# V4.net
KiCad netlist of a schematic drawn in Altium Designer
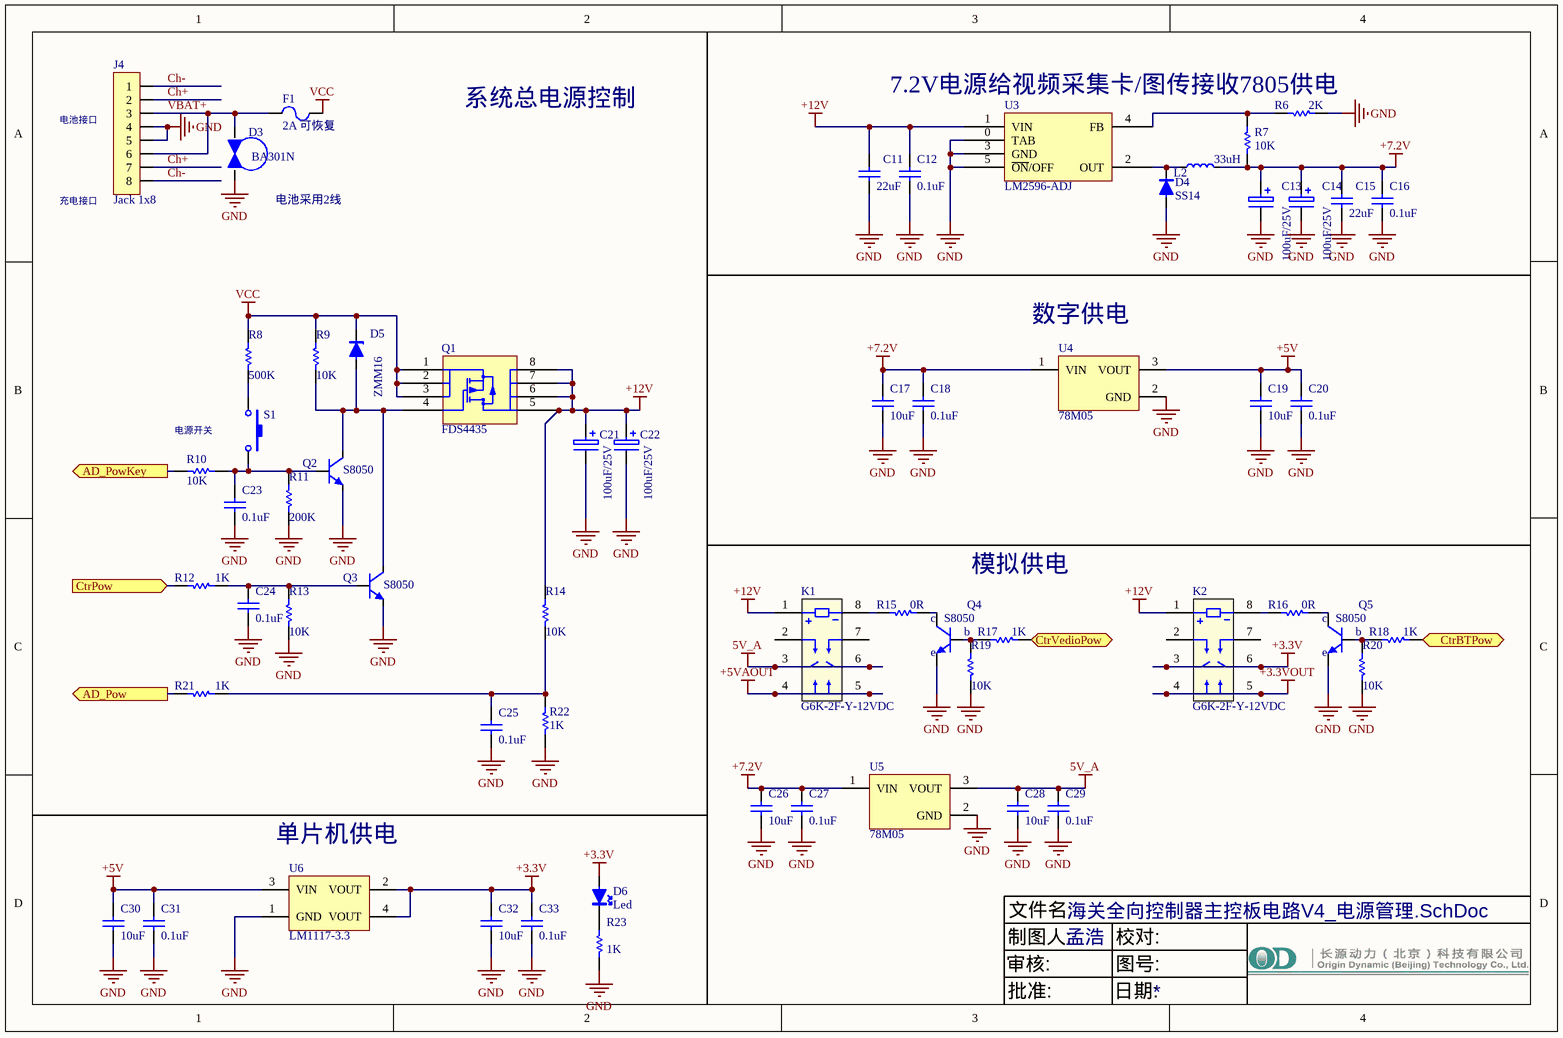
[diagram p0: 海关全向控制器主控板电路V4_电源管理.SchDoc]

(export (version "E")
  (design (tool "Eeschema 10.0.6"))
  (components
    (comp (ref "C11")
      (value "22uF")
      (footprint "C1210")
      (description "CAP")
      (fields (field (name "PUBLISHER") "Altium Limited"))
      (libsource (lib "RLCYDF") (part "CAP"))
    )
    (comp (ref "C12")
      (value "0.1uF")
      (footprint "C0805")
      (description "CAP")
      (fields (field (name "PUBLISHER") "Altium Limited"))
      (libsource (lib "RLCYDF") (part "CAP"))
    )
    (comp (ref "C13")
      (value "100uF/25V")
      (footprint "C7343")
      (description "Electrolytic Capacitor")
      (libsource (lib "*") (part "ELECTRO"))
    )
    (comp (ref "C14")
      (value "100uF/25V")
      (footprint "C7343")
      (description "Electrolytic Capacitor")
      (libsource (lib "*") (part "ELECTRO"))
    )
    (comp (ref "C15")
      (value "22uF")
      (footprint "C1210")
      (description "CAP")
      (fields (field (name "PUBLISHER") "Altium Limited"))
      (libsource (lib "RLCYDF") (part "CAP"))
    )
    (comp (ref "C16")
      (value "0.1uF")
      (footprint "C0805")
      (description "CAP")
      (fields (field (name "PUBLISHER") "Altium Limited"))
      (libsource (lib "RLCYDF") (part "CAP"))
    )
    (comp (ref "C17")
      (value "10uF")
      (footprint "C0805")
      (description "CAP")
      (fields (field (name "PUBLISHER") "Altium Limited"))
      (libsource (lib "RLCYDF") (part "CAP"))
    )
    (comp (ref "C18")
      (value "0.1uF")
      (footprint "C0805")
      (description "CAP")
      (fields (field (name "PUBLISHER") "Altium Limited"))
      (libsource (lib "RLCYDF") (part "CAP"))
    )
    (comp (ref "C19")
      (value "10uF")
      (footprint "C0805")
      (description "CAP")
      (fields (field (name "PUBLISHER") "Altium Limited"))
      (libsource (lib "RLCYDF") (part "CAP"))
    )
    (comp (ref "C20")
      (value "0.1uF")
      (footprint "C0805")
      (description "CAP")
      (fields (field (name "PUBLISHER") "Altium Limited"))
      (libsource (lib "RLCYDF") (part "CAP"))
    )
    (comp (ref "C21") (value "100uF/25V") (footprint "C7343") (libsource (lib "RLCYDF") (part "Cap Poll")))
    (comp (ref "C22") (value "100uF/25V") (footprint "C7343") (libsource (lib "RLCYDF") (part "Cap Poll")))
    (comp (ref "C23")
      (value "0.1uF")
      (footprint "C0805")
      (description "CAP")
      (fields (field (name "PUBLISHER") "Altium Limited"))
      (libsource (lib "RLCYDF") (part "CAP"))
    )
    (comp (ref "C24")
      (value "0.1uF")
      (footprint "C0805")
      (description "CAP")
      (fields (field (name "PUBLISHER") "Altium Limited"))
      (libsource (lib "RLCYDF") (part "CAP"))
    )
    (comp (ref "C25")
      (value "0.1uF")
      (footprint "C0805")
      (description "CAP")
      (fields (field (name "PUBLISHER") "Altium Limited"))
      (libsource (lib "RLCYDF") (part "CAP"))
    )
    (comp (ref "C26")
      (value "10uF")
      (footprint "C0805")
      (description "CAP")
      (fields (field (name "PUBLISHER") "Altium Limited"))
      (libsource (lib "RLCYDF") (part "CAP"))
    )
    (comp (ref "C27")
      (value "0.1uF")
      (footprint "C0805")
      (description "CAP")
      (fields (field (name "PUBLISHER") "Altium Limited"))
      (libsource (lib "RLCYDF") (part "CAP"))
    )
    (comp (ref "C28")
      (value "10uF")
      (footprint "C0805")
      (description "CAP")
      (fields (field (name "PUBLISHER") "Altium Limited"))
      (libsource (lib "RLCYDF") (part "CAP"))
    )
    (comp (ref "C29")
      (value "0.1uF")
      (footprint "C0805")
      (description "CAP")
      (fields (field (name "PUBLISHER") "Altium Limited"))
      (libsource (lib "RLCYDF") (part "CAP"))
    )
    (comp (ref "C30")
      (value "10uF")
      (footprint "C0805")
      (description "CAP")
      (fields (field (name "PUBLISHER") "Altium Limited"))
      (libsource (lib "RLCYDF") (part "CAP"))
    )
    (comp (ref "C31")
      (value "0.1uF")
      (footprint "C0805")
      (description "CAP")
      (fields (field (name "PUBLISHER") "Altium Limited"))
      (libsource (lib "RLCYDF") (part "CAP"))
    )
    (comp (ref "C32")
      (value "10uF")
      (footprint "C0805")
      (description "CAP")
      (fields (field (name "PUBLISHER") "Altium Limited"))
      (libsource (lib "RLCYDF") (part "CAP"))
    )
    (comp (ref "C33")
      (value "0.1uF")
      (footprint "C0805")
      (description "CAP")
      (fields (field (name "PUBLISHER") "Altium Limited"))
      (libsource (lib "RLCYDF") (part "CAP"))
    )
    (comp (ref "D3") (value "BA301N") (footprint "BA301N") (libsource (lib "MhSchlib") (part "BA301N")))
    (comp (ref "D4")
      (value "SS14")
      (footprint "SMA")
      (description "Silicon Epitaxial Planar Diodes")
      (libsource (lib "RLCYDF") (part "Diode-Switch"))
    )
    (comp (ref "D5")
      (value "ZMM16")
      (footprint "SOD-80-S")
      (description "Small Signal Zener Diodes")
      (libsource (lib "RLCYDF") (part "DIODE-ZENER"))
    )
    (comp (ref "D6")
      (value "Led")
      (footprint "LED0805")
      (description "light emitted diode")
      (libsource (lib "RLCYDF") (part "Led"))
    )
    (comp (ref "F1") (value "2A 可恢复") (footprint "F1812") (libsource (lib "RLCYDF") (part "Fuse1")))
    (comp (ref "J4")
      (value "Jack 1x8")
      (footprint "Pow-8P-M")
      (description "插座")
      (libsource (lib "Connector") (part "Jack 1x8"))
    )
    (comp (ref "K1")
      (value "G6K-2F-Y-12VDC")
      (footprint "G6K-2F-Y")
      (libsource (lib "海关全向本体电路板V3") (part "G6K-2F-Y"))
    )
    (comp (ref "K2")
      (value "G6K-2F-Y-12VDC")
      (footprint "G6K-2F-Y")
      (libsource (lib "海关全向本体电路板V3") (part "G6K-2F-Y"))
    )
    (comp (ref "L2")
      (value "33uH")
      (footprint "L6.6*7.1mm")
      (description "INDUCTOR")
      (fields (field (name "PUBLISHER") "Altium Limited"))
      (libsource (lib "RLCYDF") (part "INDUCTOR"))
    )
    (comp (ref "Q1") (value "FDS4435") (footprint "SO8") (libsource (lib "OmniDirCtr") (part "FDS4435")))
    (comp (ref "Q2")
      (value "S8050")
      (footprint "SOT-23")
      (description "NPN General Purpose Amplifier")
      (fields (field (name "PUBLISHER") "Altium Limited"))
      (libsource (lib "Bdmc4810") (part "NPN"))
    )
    (comp (ref "Q3")
      (value "S8050")
      (footprint "SOT-23")
      (description "NPN General Purpose Amplifier")
      (fields (field (name "PUBLISHER") "Altium Limited"))
      (libsource (lib "Bdmc4810") (part "NPN"))
    )
    (comp (ref "Q4")
      (value "S8050")
      (footprint "SOT-23")
      (description "NPN triode, 0.5A Max")
      (libsource (lib "RLCYDF") (part "S8050"))
    )
    (comp (ref "Q5")
      (value "S8050")
      (footprint "SOT-23")
      (description "NPN triode, 0.5A Max")
      (libsource (lib "RLCYDF") (part "S8050"))
    )
    (comp (ref "R6") (value "2K") (footprint "R0805") (libsource (lib "RLCYDF") (part "Res")))
    (comp (ref "R7") (value "10K") (footprint "R0805") (libsource (lib "RLCYDF") (part "Res")))
    (comp (ref "R8") (value "500K") (footprint "R0805") (libsource (lib "RLCYDF") (part "Res")))
    (comp (ref "R9") (value "10K") (footprint "R0805") (libsource (lib "RLCYDF") (part "Res")))
    (comp (ref "R10") (value "10K") (footprint "R0805") (libsource (lib "RLCYDF") (part "Res")))
    (comp (ref "R11") (value "200K") (footprint "R0805") (libsource (lib "RLCYDF") (part "Res")))
    (comp (ref "R12") (value "1K") (footprint "R0805") (libsource (lib "RLCYDF") (part "Res")))
    (comp (ref "R13") (value "10K") (footprint "R0805") (libsource (lib "RLCYDF") (part "Res")))
    (comp (ref "R14") (value "10K") (footprint "R0805") (libsource (lib "RLCYDF") (part "Res")))
    (comp (ref "R15") (value "0R") (footprint "R0805") (libsource (lib "RLCYDF") (part "Res")))
    (comp (ref "R16") (value "0R") (footprint "R0805") (libsource (lib "RLCYDF") (part "Res")))
    (comp (ref "R17") (value "1K") (footprint "R0805") (libsource (lib "RLCYDF") (part "Res")))
    (comp (ref "R18") (value "1K") (footprint "R0805") (libsource (lib "RLCYDF") (part "Res")))
    (comp (ref "R19") (value "10K") (footprint "R0805") (libsource (lib "RLCYDF") (part "Res")))
    (comp (ref "R20") (value "10K") (footprint "R0805") (libsource (lib "RLCYDF") (part "Res")))
    (comp (ref "R21") (value "1K") (footprint "R0805") (libsource (lib "RLCYDF") (part "Res")))
    (comp (ref "R22") (value "1K") (footprint "R0805") (libsource (lib "RLCYDF") (part "Res")))
    (comp (ref "R23") (value "1K") (footprint "R0805") (libsource (lib "RLCYDF") (part "Res")))
    (comp (ref "S1")
      (value "SW-PB")
      (footprint "35363-0260")
      (description "Switch")
      (fields (field (name "PUBLISHER") "Altium Limited"))
      (libsource (lib "海关全向控制器主控板V3") (part "SW-PB"))
    )
    (comp (ref "U3")
      (value "LM2596-ADJ")
      (footprint "TO-263-5")
      (description "LM2596-5;LM2576-5")
      (libsource (lib "chip") (part "LM25x6-5"))
    )
    (comp (ref "U4") (value "78M05") (footprint "TO-252") (libsource (lib "chip") (part "78M05")))
    (comp (ref "U5") (value "78M05") (footprint "TO-252") (libsource (lib "chip") (part "78M05")))
    (comp (ref "U6")
      (value "LM1117-3.3")
      (footprint "SOT-223")
      (description "800mA Linear Voltage Regulator")
      (libsource (lib "chip") (part "LM1117"))
    )
  )
  (nets
    (net (code "1") (name "+3.3V") (class "Default")
      (node (ref "C32") (pin "1") (pinfunction "1_1") (pintype "passive"))
      (node (ref "C33") (pin "1") (pinfunction "1_1") (pintype "passive"))
      (node (ref "D6") (pin "1") (pinfunction "A_1") (pintype "passive"))
      (node (ref "K2") (pin "3") (pinfunction "3_3") (pintype "passive"))
      (node (ref "K2") (pin "6") (pinfunction "6_6") (pintype "passive"))
      (node (ref "U6") (pin "2") (pinfunction "VOUT_2") (pintype "passive"))
      (node (ref "U6") (pin "4") (pinfunction "VOUT_4") (pintype "passive"))
    )
    (net (code "2") (name "+3.3VOUT") (class "Default")
      (node (ref "K2") (pin "4") (pinfunction "4_4") (pintype "passive"))
      (node (ref "K2") (pin "5") (pinfunction "5_5") (pintype "passive"))
    )
    (net (code "3") (name "+5V") (class "Default")
      (node (ref "C19") (pin "1") (pinfunction "1_1") (pintype "passive"))
      (node (ref "C20") (pin "1") (pinfunction "1_1") (pintype "passive"))
      (node (ref "C30") (pin "1") (pinfunction "1_1") (pintype "passive"))
      (node (ref "C31") (pin "1") (pinfunction "1_1") (pintype "passive"))
      (node (ref "U4") (pin "3") (pinfunction "VOUT_3") (pintype "passive"))
      (node (ref "U6") (pin "3") (pinfunction "VIN_3") (pintype "passive"))
    )
    (net (code "4") (name "+5VAOUT") (class "Default")
      (node (ref "K1") (pin "4") (pinfunction "4_4") (pintype "passive"))
      (node (ref "K1") (pin "5") (pinfunction "5_5") (pintype "passive"))
    )
    (net (code "5") (name "+7.2V") (class "Default")
      (node (ref "C13") (pin "1") (pinfunction "1_1") (pintype "passive"))
      (node (ref "C14") (pin "1") (pinfunction "1_1") (pintype "passive"))
      (node (ref "C15") (pin "1") (pinfunction "1_1") (pintype "passive"))
      (node (ref "C16") (pin "2") (pinfunction "2_2") (pintype "passive"))
      (node (ref "C17") (pin "1") (pinfunction "1_1") (pintype "passive"))
      (node (ref "C18") (pin "1") (pinfunction "1_1") (pintype "passive"))
      (node (ref "C26") (pin "1") (pinfunction "1_1") (pintype "passive"))
      (node (ref "C27") (pin "1") (pinfunction "1_1") (pintype "passive"))
      (node (ref "L2") (pin "2") (pinfunction "2_2") (pintype "passive"))
      (node (ref "R7") (pin "2") (pinfunction "2_2") (pintype "passive"))
      (node (ref "U4") (pin "1") (pinfunction "VIN_1") (pintype "passive"))
      (node (ref "U5") (pin "1") (pinfunction "VIN_1") (pintype "passive"))
    )
    (net (code "6") (name "+12V") (class "Default")
      (node (ref "C11") (pin "1") (pinfunction "1_1") (pintype "passive"))
      (node (ref "C12") (pin "2") (pinfunction "2_2") (pintype "passive"))
      (node (ref "C21") (pin "1") (pinfunction "1_1") (pintype "passive"))
      (node (ref "C22") (pin "1") (pinfunction "1_1") (pintype "passive"))
      (node (ref "K1") (pin "1") (pinfunction "1_1") (pintype "passive"))
      (node (ref "K2") (pin "1") (pinfunction "1_1") (pintype "passive"))
      (node (ref "Q1") (pin "5") (pintype "passive"))
      (node (ref "Q1") (pin "6") (pintype "passive"))
      (node (ref "Q1") (pin "7") (pintype "passive"))
      (node (ref "Q1") (pin "8") (pintype "passive"))
      (node (ref "R14") (pin "1") (pinfunction "1_1") (pintype "passive"))
      (node (ref "U3") (pin "1") (pinfunction "VIN_1") (pintype "passive"))
    )
    (net (code "7") (name "/AD_Pow") (class "Default")
      (node (ref "R21") (pin "1") (pinfunction "1_1") (pintype "passive"))
    )
    (net (code "8") (name "/AD_PowKey") (class "Default")
      (node (ref "R10") (pin "1") (pinfunction "1_1") (pintype "passive"))
    )
    (net (code "9") (name "/Ch+") (class "Default")
      (node (ref "J4") (pin "2") (pinfunction "2_2") (pintype "passive"))
      (node (ref "J4") (pin "7") (pinfunction "7_7") (pintype "passive"))
    )
    (net (code "10") (name "/Ch-") (class "Default")
      (node (ref "J4") (pin "1") (pinfunction "1_1") (pintype "passive"))
      (node (ref "J4") (pin "8") (pinfunction "8_8") (pintype "passive"))
    )
    (net (code "11") (name "/CtrBTPow") (class "Default")
      (node (ref "R18") (pin "2") (pinfunction "2_2") (pintype "passive"))
    )
    (net (code "12") (name "/CtrPow") (class "Default")
      (node (ref "R12") (pin "1") (pinfunction "1_1") (pintype "passive"))
    )
    (net (code "13") (name "/CtrVedioPow") (class "Default")
      (node (ref "R17") (pin "2") (pinfunction "2_2") (pintype "passive"))
    )
    (net (code "14") (name "/VBAT+") (class "Default")
      (node (ref "D3") (pin "1") (pinfunction "1_1") (pintype "passive"))
      (node (ref "F1") (pin "1") (pinfunction "1_1") (pintype "passive"))
      (node (ref "J4") (pin "3") (pinfunction "3_3") (pintype "passive"))
      (node (ref "J4") (pin "6") (pinfunction "6_6") (pintype "passive"))
    )
    (net (code "15") (name "5V_A") (class "Default")
      (node (ref "C28") (pin "1") (pinfunction "1_1") (pintype "passive"))
      (node (ref "C29") (pin "1") (pinfunction "1_1") (pintype "passive"))
      (node (ref "K1") (pin "3") (pinfunction "3_3") (pintype "passive"))
      (node (ref "K1") (pin "6") (pinfunction "6_6") (pintype "passive"))
      (node (ref "U5") (pin "3") (pinfunction "VOUT_3") (pintype "passive"))
    )
    (net (code "16") (name "GND") (class "Default")
      (node (ref "C11") (pin "2") (pinfunction "2_2") (pintype "passive"))
      (node (ref "C12") (pin "1") (pinfunction "1_1") (pintype "passive"))
      (node (ref "C13") (pin "2") (pinfunction "2_2") (pintype "passive"))
      (node (ref "C14") (pin "2") (pinfunction "2_2") (pintype "passive"))
      (node (ref "C15") (pin "2") (pinfunction "2_2") (pintype "passive"))
      (node (ref "C16") (pin "1") (pinfunction "1_1") (pintype "passive"))
      (node (ref "C17") (pin "2") (pinfunction "2_2") (pintype "passive"))
      (node (ref "C18") (pin "2") (pinfunction "2_2") (pintype "passive"))
      (node (ref "C19") (pin "2") (pinfunction "2_2") (pintype "passive"))
      (node (ref "C20") (pin "2") (pinfunction "2_2") (pintype "passive"))
      (node (ref "C21") (pin "2") (pinfunction "2_2") (pintype "passive"))
      (node (ref "C22") (pin "2") (pinfunction "2_2") (pintype "passive"))
      (node (ref "C23") (pin "2") (pinfunction "2_2") (pintype "passive"))
      (node (ref "C24") (pin "2") (pinfunction "2_2") (pintype "passive"))
      (node (ref "C25") (pin "2") (pinfunction "2_2") (pintype "passive"))
      (node (ref "C26") (pin "2") (pinfunction "2_2") (pintype "passive"))
      (node (ref "C27") (pin "2") (pinfunction "2_2") (pintype "passive"))
      (node (ref "C28") (pin "2") (pinfunction "2_2") (pintype "passive"))
      (node (ref "C29") (pin "2") (pinfunction "2_2") (pintype "passive"))
      (node (ref "C30") (pin "2") (pinfunction "2_2") (pintype "passive"))
      (node (ref "C31") (pin "2") (pinfunction "2_2") (pintype "passive"))
      (node (ref "C32") (pin "2") (pinfunction "2_2") (pintype "passive"))
      (node (ref "C33") (pin "2") (pinfunction "2_2") (pintype "passive"))
      (node (ref "D3") (pin "2") (pinfunction "2_2") (pintype "passive"))
      (node (ref "D4") (pin "1") (pinfunction "A_1") (pintype "passive"))
      (node (ref "J4") (pin "4") (pinfunction "4_4") (pintype "passive"))
      (node (ref "J4") (pin "5") (pinfunction "5_5") (pintype "passive"))
      (node (ref "Q2") (pin "2") (pinfunction "E_2") (pintype "passive"))
      (node (ref "Q3") (pin "2") (pinfunction "E_2") (pintype "passive"))
      (node (ref "Q4") (pin "2") (pinfunction "e_2") (pintype "passive"))
      (node (ref "Q5") (pin "2") (pinfunction "e_2") (pintype "passive"))
      (node (ref "R11") (pin "2") (pinfunction "2_2") (pintype "passive"))
      (node (ref "R13") (pin "2") (pinfunction "2_2") (pintype "passive"))
      (node (ref "R19") (pin "2") (pinfunction "2_2") (pintype "passive"))
      (node (ref "R20") (pin "2") (pinfunction "2_2") (pintype "passive"))
      (node (ref "R22") (pin "1") (pinfunction "1_1") (pintype "passive"))
      (node (ref "R23") (pin "2") (pinfunction "2_2") (pintype "passive"))
      (node (ref "R6") (pin "1") (pinfunction "1_1") (pintype "passive"))
      (node (ref "U3") (pin "0") (pinfunction "TAB_0") (pintype "passive"))
      (node (ref "U3") (pin "3") (pinfunction "GND_3") (pintype "passive"))
      (node (ref "U3") (pin "5") (pinfunction "~{ON}/OFF_5") (pintype "passive"))
      (node (ref "U4") (pin "2") (pinfunction "GND_2") (pintype "passive"))
      (node (ref "U5") (pin "2") (pinfunction "GND_2") (pintype "passive"))
      (node (ref "U6") (pin "1") (pinfunction "GND_1") (pintype "passive"))
    )
    (net (code "17") (name "Net-(C25-Pad1)") (class "Default")
      (node (ref "C25") (pin "1") (pinfunction "1_1") (pintype "passive"))
      (node (ref "R14") (pin "2") (pinfunction "2_2") (pintype "passive"))
      (node (ref "R21") (pin "2") (pinfunction "2_2") (pintype "passive"))
      (node (ref "R22") (pin "2") (pinfunction "2_2") (pintype "passive"))
    )
    (net (code "18") (name "Net-(D4-K)") (class "Default")
      (node (ref "D4") (pin "2") (pinfunction "K_2") (pintype "passive"))
      (node (ref "L2") (pin "1") (pinfunction "1_1") (pintype "passive"))
      (node (ref "U3") (pin "2") (pinfunction "OUT_2") (pintype "passive"))
    )
    (net (code "19") (name "Net-(D5-A)") (class "Default")
      (node (ref "D5") (pin "1") (pinfunction "A_1") (pintype "passive"))
      (node (ref "Q1") (pin "4") (pintype "passive"))
      (node (ref "Q2") (pin "3") (pinfunction "C_3") (pintype "passive"))
      (node (ref "Q3") (pin "3") (pinfunction "C_3") (pintype "passive"))
      (node (ref "R9") (pin "2") (pinfunction "2_2") (pintype "passive"))
    )
    (net (code "20") (name "Net-(D6-K)") (class "Default")
      (node (ref "D6") (pin "2") (pinfunction "K_2") (pintype "passive"))
      (node (ref "R23") (pin "1") (pinfunction "1_1") (pintype "passive"))
    )
    (net (code "21") (name "Net-(K1-Pad8)") (class "Default")
      (node (ref "K1") (pin "8") (pinfunction "8_8") (pintype "passive"))
      (node (ref "R15") (pin "1") (pinfunction "1_1") (pintype "passive"))
    )
    (net (code "22") (name "Net-(K2-Pad8)") (class "Default")
      (node (ref "K2") (pin "8") (pinfunction "8_8") (pintype "passive"))
      (node (ref "R16") (pin "1") (pinfunction "1_1") (pintype "passive"))
    )
    (net (code "23") (name "Net-(Q2-B)") (class "Default")
      (node (ref "C23") (pin "1") (pinfunction "1_1") (pintype "passive"))
      (node (ref "Q2") (pin "1") (pinfunction "B_1") (pintype "passive"))
      (node (ref "R10") (pin "2") (pinfunction "2_2") (pintype "passive"))
      (node (ref "R11") (pin "1") (pinfunction "1_1") (pintype "passive"))
      (node (ref "S1") (pin "2") (pinfunction "2_2") (pintype "passive"))
    )
    (net (code "24") (name "Net-(Q3-B)") (class "Default")
      (node (ref "C24") (pin "1") (pinfunction "1_1") (pintype "passive"))
      (node (ref "Q3") (pin "1") (pinfunction "B_1") (pintype "passive"))
      (node (ref "R12") (pin "2") (pinfunction "2_2") (pintype "passive"))
      (node (ref "R13") (pin "1") (pinfunction "1_1") (pintype "passive"))
    )
    (net (code "25") (name "Net-(Q4-b)") (class "Default")
      (node (ref "Q4") (pin "1") (pinfunction "b_1") (pintype "passive"))
      (node (ref "R17") (pin "1") (pinfunction "1_1") (pintype "passive"))
      (node (ref "R19") (pin "1") (pinfunction "1_1") (pintype "passive"))
    )
    (net (code "26") (name "Net-(Q4-c)") (class "Default")
      (node (ref "Q4") (pin "3") (pinfunction "c_3") (pintype "passive"))
      (node (ref "R15") (pin "2") (pinfunction "2_2") (pintype "passive"))
    )
    (net (code "27") (name "Net-(Q5-b)") (class "Default")
      (node (ref "Q5") (pin "1") (pinfunction "b_1") (pintype "passive"))
      (node (ref "R18") (pin "1") (pinfunction "1_1") (pintype "passive"))
      (node (ref "R20") (pin "1") (pinfunction "1_1") (pintype "passive"))
    )
    (net (code "28") (name "Net-(Q5-c)") (class "Default")
      (node (ref "Q5") (pin "3") (pinfunction "c_3") (pintype "passive"))
      (node (ref "R16") (pin "2") (pinfunction "2_2") (pintype "passive"))
    )
    (net (code "29") (name "Net-(R8-Pad2)") (class "Default")
      (node (ref "R8") (pin "2") (pinfunction "2_2") (pintype "passive"))
      (node (ref "S1") (pin "1") (pinfunction "1_1") (pintype "passive"))
    )
    (net (code "30") (name "Net-(U3-FB)") (class "Default")
      (node (ref "R6") (pin "2") (pinfunction "2_2") (pintype "passive"))
      (node (ref "R7") (pin "1") (pinfunction "1_1") (pintype "passive"))
      (node (ref "U3") (pin "4") (pinfunction "FB_4") (pintype "passive"))
    )
    (net (code "31") (name "VCC") (class "Default")
      (node (ref "D5") (pin "2") (pinfunction "K_2") (pintype "passive"))
      (node (ref "F1") (pin "2") (pinfunction "2_2") (pintype "passive"))
      (node (ref "Q1") (pin "1") (pintype "passive"))
      (node (ref "Q1") (pin "2") (pintype "passive"))
      (node (ref "Q1") (pin "3") (pintype "passive"))
      (node (ref "R8") (pin "1") (pinfunction "1_1") (pintype "passive"))
      (node (ref "R9") (pin "1") (pinfunction "1_1") (pintype "passive"))
    )
    (net (code "32") (name "unconnected-(K1-Pad2)") (class "Default")
      (node (ref "K1") (pin "2") (pinfunction "2_2") (pintype "passive"))
    )
    (net (code "33") (name "unconnected-(K1-Pad7)") (class "Default")
      (node (ref "K1") (pin "7") (pinfunction "7_7") (pintype "passive"))
    )
    (net (code "34") (name "unconnected-(K2-Pad2)") (class "Default")
      (node (ref "K2") (pin "2") (pinfunction "2_2") (pintype "passive"))
    )
    (net (code "35") (name "unconnected-(K2-Pad7)") (class "Default")
      (node (ref "K2") (pin "7") (pinfunction "7_7") (pintype "passive"))
    )
  )
)
